# Top.net
KiCad netlist of a schematic drawn in EAGLE
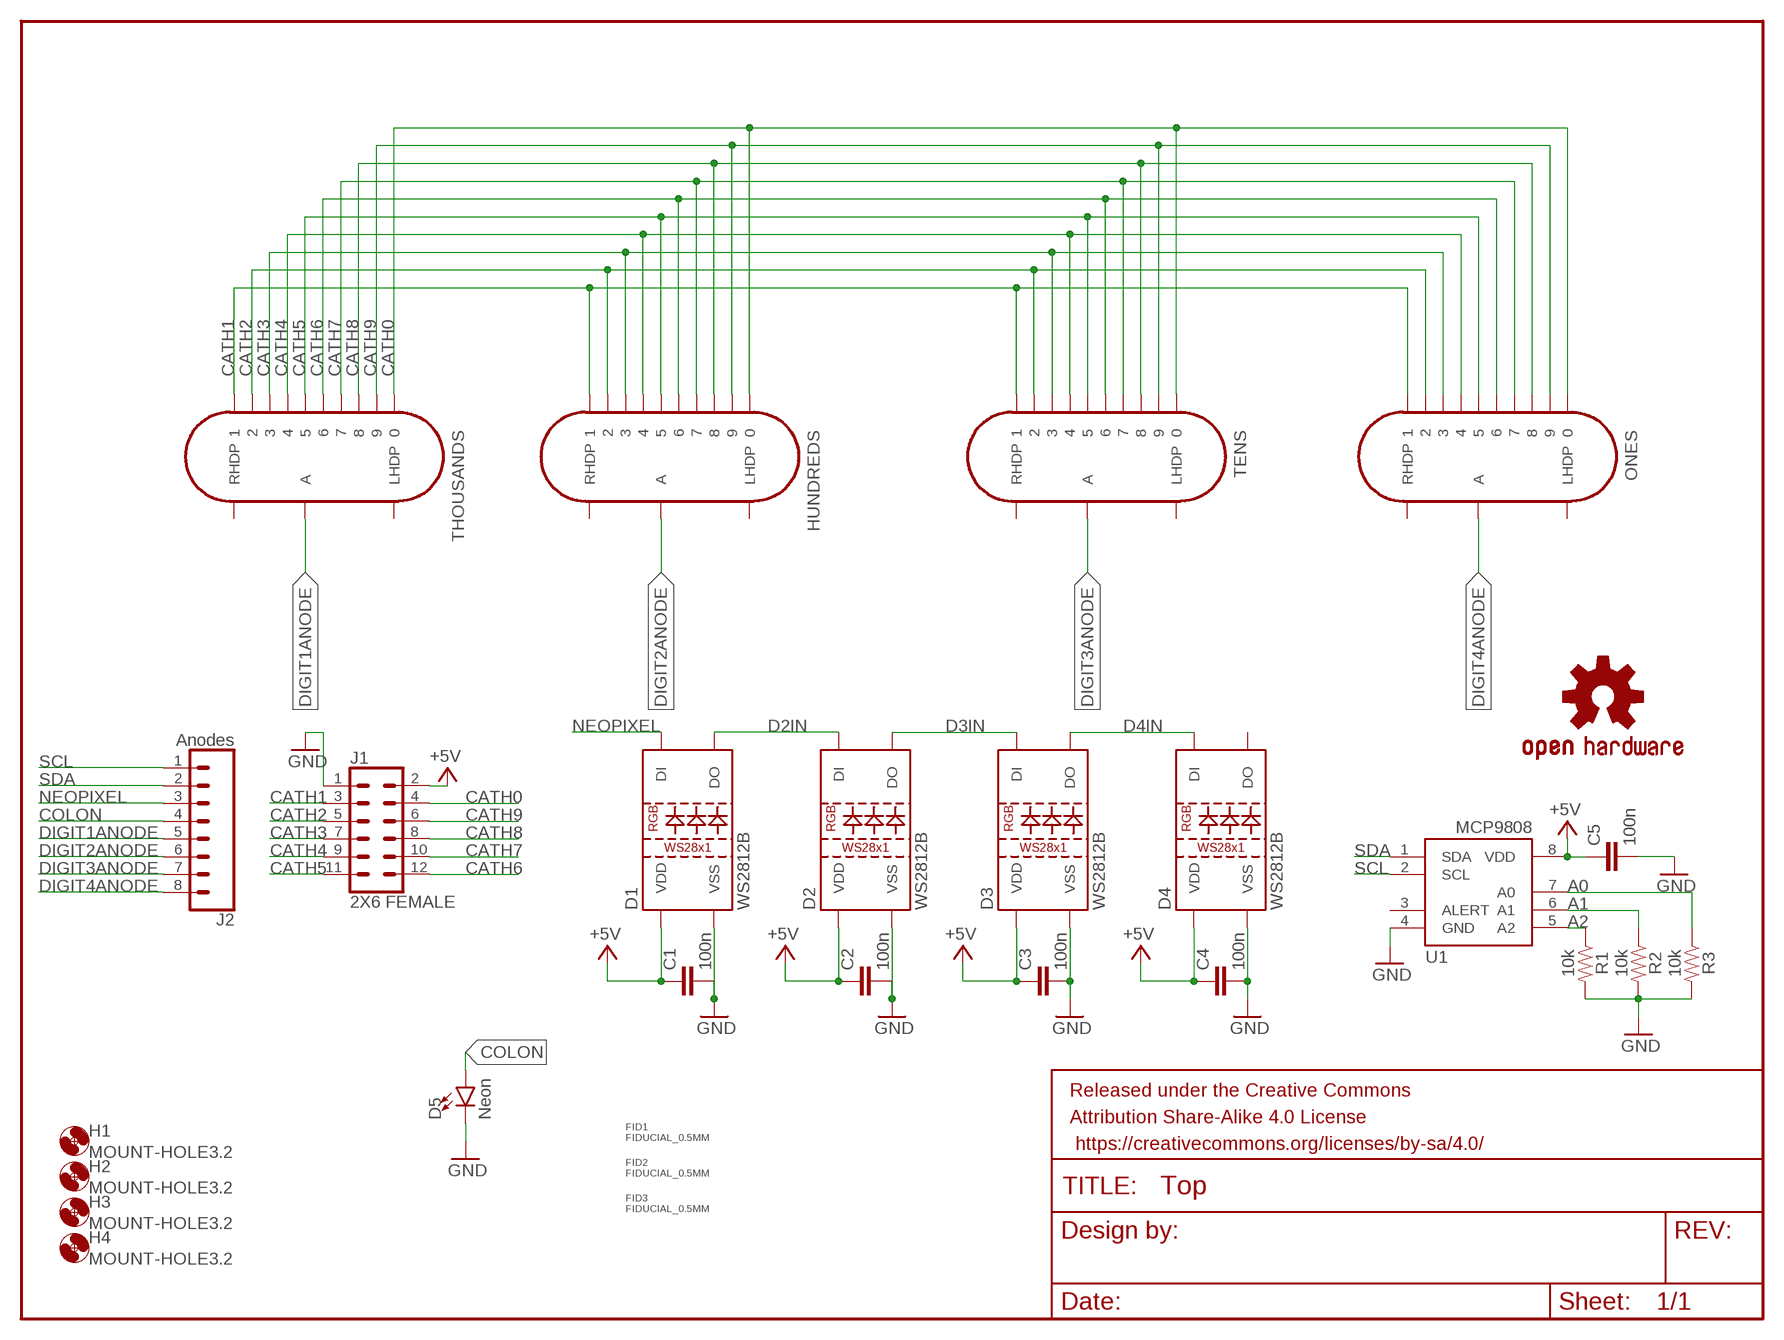
[diagram p0: schematic, sheet 1]

(export (version "E")
  (design (tool "Eeschema 10.0.6"))
  (components
    (comp (ref "C1")
      (value "100n")
      (footprint "eagle-import:0805")
      (libsource (lib "eagle-import") (part "2.2UF-0805-25V-(+80/-20%)"))
    )
    (comp (ref "C2")
      (value "100n")
      (footprint "eagle-import:0805")
      (libsource (lib "eagle-import") (part "2.2UF-0805-25V-(+80/-20%)"))
    )
    (comp (ref "C3")
      (value "100n")
      (footprint "eagle-import:0805")
      (libsource (lib "eagle-import") (part "2.2UF-0805-25V-(+80/-20%)"))
    )
    (comp (ref "C4")
      (value "100n")
      (footprint "eagle-import:0805")
      (libsource (lib "eagle-import") (part "2.2UF-0805-25V-(+80/-20%)"))
    )
    (comp (ref "C5")
      (value "100n")
      (footprint "eagle-import:0805")
      (libsource (lib "eagle-import") (part "2.2UF-0805-25V-(+80/-20%)"))
    )
    (comp (ref "D1")
      (value "WS2812B")
      (footprint "eagle-import:WS2812B")
      (libsource (lib "eagle-import") (part "WS2812B"))
    )
    (comp (ref "D2")
      (value "WS2812B")
      (footprint "eagle-import:WS2812B")
      (libsource (lib "eagle-import") (part "WS2812B"))
    )
    (comp (ref "D3")
      (value "WS2812B")
      (footprint "eagle-import:WS2812B")
      (libsource (lib "eagle-import") (part "WS2812B"))
    )
    (comp (ref "D4")
      (value "WS2812B")
      (footprint "eagle-import:WS2812B")
      (libsource (lib "eagle-import") (part "WS2812B"))
    )
    (comp (ref "D5")
      (value "Neon")
      (footprint "eagle-import:LED_5MM")
      (libsource (lib "eagle-import") (part "LED5MM"))
    )
    (comp (ref "FID1")
      (value "FIDUCIAL_0.5MM")
      (footprint "eagle-import:FIDUCIAL_0.5MM")
      (fields (field (name "HOUSEPART") "NO"))
      (libsource (lib "eagle-import") (part "FIDUCIAL_0.5MM"))
    )
    (comp (ref "FID2")
      (value "FIDUCIAL_0.5MM")
      (footprint "eagle-import:FIDUCIAL_0.5MM")
      (fields (field (name "HOUSEPART") "NO"))
      (libsource (lib "eagle-import") (part "FIDUCIAL_0.5MM"))
    )
    (comp (ref "FID3")
      (value "FIDUCIAL_0.5MM")
      (footprint "eagle-import:FIDUCIAL_0.5MM")
      (fields (field (name "HOUSEPART") "NO"))
      (libsource (lib "eagle-import") (part "FIDUCIAL_0.5MM"))
    )
    (comp (ref "FRAME1")
      (value "FRAME-LETTER")
      (footprint "eagle-import:CREATIVE_COMMONS")
      (libsource (lib "eagle-import") (part "FRAME-LETTER"))
    )
    (comp (ref "H1")
      (value "MOUNT-HOLE3.2")
      (footprint "eagle-import:3,2")
      (libsource (lib "eagle-import") (part "MOUNT-HOLE3.2"))
    )
    (comp (ref "H2")
      (value "MOUNT-HOLE3.2")
      (footprint "eagle-import:3,2")
      (libsource (lib "eagle-import") (part "MOUNT-HOLE3.2"))
    )
    (comp (ref "H3")
      (value "MOUNT-HOLE3.2")
      (footprint "eagle-import:3,2")
      (libsource (lib "eagle-import") (part "MOUNT-HOLE3.2"))
    )
    (comp (ref "H4")
      (value "MOUNT-HOLE3.2")
      (footprint "eagle-import:3,2")
      (libsource (lib "eagle-import") (part "MOUNT-HOLE3.2"))
    )
    (comp (ref "HUNDREDS")
      (value "IN-14")
      (footprint "eagle-import:IN-14")
      (libsource (lib "eagle-import") (part "IN-14"))
    )
    (comp (ref "J1")
      (value "2X6 FEMALE")
      (footprint "eagle-import:2X6_NOSILK")
      (libsource (lib "eagle-import") (part "CONN_06X2NO_SILK"))
    )
    (comp (ref "J2")
      (value "Anodes")
      (footprint "eagle-import:1X08_NO_SILK")
      (libsource (lib "eagle-import") (part "CONN_08NO_SILK_FEMALE_PTH"))
    )
    (comp (ref "LOGO1")
      (value "OSHW-LOGOM")
      (footprint "eagle-import:OSHW-LOGO-M")
      (libsource (lib "eagle-import") (part "OSHW-LOGOM"))
    )
    (comp (ref "ONES")
      (value "IN-14")
      (footprint "eagle-import:IN-14")
      (libsource (lib "eagle-import") (part "IN-14"))
    )
    (comp (ref "R1")
      (value "10k")
      (footprint "eagle-import:0805")
      (libsource (lib "eagle-import") (part "0.75OHM-0805-1/4W-1%"))
    )
    (comp (ref "R2")
      (value "10k")
      (footprint "eagle-import:0805")
      (libsource (lib "eagle-import") (part "0.75OHM-0805-1/4W-1%"))
    )
    (comp (ref "R3")
      (value "10k")
      (footprint "eagle-import:0805")
      (libsource (lib "eagle-import") (part "0.75OHM-0805-1/4W-1%"))
    )
    (comp (ref "TENS")
      (value "IN-14")
      (footprint "eagle-import:IN-14")
      (libsource (lib "eagle-import") (part "IN-14"))
    )
    (comp (ref "THOUSANDS")
      (value "IN-14")
      (footprint "eagle-import:IN-14")
      (libsource (lib "eagle-import") (part "IN-14"))
    )
    (comp (ref "U1")
      (value "MCP9808-E/MS")
      (footprint "eagle-import:MSOP8_0.65MM")
      (libsource (lib "eagle-import") (part "MCP9808-E/MS"))
    )
  )
  (nets
    (net (code "1") (name "+5V") (class "Default")
      (node (ref "C1") (pin "1") (pinfunction "1_1") (pintype "passive"))
      (node (ref "C2") (pin "1") (pinfunction "1_1") (pintype "passive"))
      (node (ref "C3") (pin "1") (pinfunction "1_1") (pintype "passive"))
      (node (ref "C4") (pin "1") (pinfunction "1_1") (pintype "passive"))
      (node (ref "C5") (pin "1") (pinfunction "1_1") (pintype "passive"))
      (node (ref "D1") (pin "1") (pinfunction "VDD_1") (pintype "bidirectional"))
      (node (ref "D2") (pin "1") (pinfunction "VDD_1") (pintype "bidirectional"))
      (node (ref "D3") (pin "1") (pinfunction "VDD_1") (pintype "bidirectional"))
      (node (ref "D4") (pin "1") (pinfunction "VDD_1") (pintype "bidirectional"))
      (node (ref "J1") (pin "2") (pinfunction "2_2") (pintype "passive"))
      (node (ref "U1") (pin "8") (pinfunction "VDD_8") (pintype "power_in"))
    )
    (net (code "2") (name "/A0") (class "Default")
      (node (ref "R3") (pin "1") (pinfunction "1_1") (pintype "passive"))
      (node (ref "U1") (pin "7") (pinfunction "A0_7") (pintype "input"))
    )
    (net (code "3") (name "/A1") (class "Default")
      (node (ref "R2") (pin "1") (pinfunction "1_1") (pintype "passive"))
      (node (ref "U1") (pin "6") (pinfunction "A1_6") (pintype "input"))
    )
    (net (code "4") (name "/A2") (class "Default")
      (node (ref "R1") (pin "1") (pinfunction "1_1") (pintype "passive"))
      (node (ref "U1") (pin "5") (pinfunction "A2_5") (pintype "input"))
    )
    (net (code "5") (name "/CATH0") (class "Default")
      (node (ref "HUNDREDS") (pin "1") (pinfunction "0_1") (pintype "bidirectional"))
      (node (ref "J1") (pin "4") (pinfunction "4_4") (pintype "passive"))
      (node (ref "ONES") (pin "1") (pinfunction "0_1") (pintype "bidirectional"))
      (node (ref "TENS") (pin "1") (pinfunction "0_1") (pintype "bidirectional"))
      (node (ref "THOUSANDS") (pin "1") (pinfunction "0_1") (pintype "bidirectional"))
    )
    (net (code "6") (name "/CATH1") (class "Default")
      (node (ref "HUNDREDS") (pin "0") (pinfunction "1_0") (pintype "bidirectional"))
      (node (ref "J1") (pin "3") (pinfunction "3_3") (pintype "passive"))
      (node (ref "ONES") (pin "0") (pinfunction "1_0") (pintype "bidirectional"))
      (node (ref "TENS") (pin "0") (pinfunction "1_0") (pintype "bidirectional"))
      (node (ref "THOUSANDS") (pin "0") (pinfunction "1_0") (pintype "bidirectional"))
    )
    (net (code "7") (name "/CATH2") (class "Default")
      (node (ref "HUNDREDS") (pin "9") (pinfunction "2_9") (pintype "bidirectional"))
      (node (ref "J1") (pin "5") (pinfunction "5_5") (pintype "passive"))
      (node (ref "ONES") (pin "9") (pinfunction "2_9") (pintype "bidirectional"))
      (node (ref "TENS") (pin "9") (pinfunction "2_9") (pintype "bidirectional"))
      (node (ref "THOUSANDS") (pin "9") (pinfunction "2_9") (pintype "bidirectional"))
    )
    (net (code "8") (name "/CATH3") (class "Default")
      (node (ref "HUNDREDS") (pin "8") (pinfunction "3_8") (pintype "bidirectional"))
      (node (ref "J1") (pin "7") (pinfunction "7_7") (pintype "passive"))
      (node (ref "ONES") (pin "8") (pinfunction "3_8") (pintype "bidirectional"))
      (node (ref "TENS") (pin "8") (pinfunction "3_8") (pintype "bidirectional"))
      (node (ref "THOUSANDS") (pin "8") (pinfunction "3_8") (pintype "bidirectional"))
    )
    (net (code "9") (name "/CATH4") (class "Default")
      (node (ref "HUNDREDS") (pin "7") (pinfunction "4_7") (pintype "bidirectional"))
      (node (ref "J1") (pin "9") (pinfunction "9_9") (pintype "passive"))
      (node (ref "ONES") (pin "7") (pinfunction "4_7") (pintype "bidirectional"))
      (node (ref "TENS") (pin "7") (pinfunction "4_7") (pintype "bidirectional"))
      (node (ref "THOUSANDS") (pin "7") (pinfunction "4_7") (pintype "bidirectional"))
    )
    (net (code "10") (name "/CATH5") (class "Default")
      (node (ref "HUNDREDS") (pin "6") (pinfunction "5_6") (pintype "bidirectional"))
      (node (ref "J1") (pin "11") (pinfunction "11_11") (pintype "passive"))
      (node (ref "ONES") (pin "6") (pinfunction "5_6") (pintype "bidirectional"))
      (node (ref "TENS") (pin "6") (pinfunction "5_6") (pintype "bidirectional"))
      (node (ref "THOUSANDS") (pin "6") (pinfunction "5_6") (pintype "bidirectional"))
    )
    (net (code "11") (name "/CATH6") (class "Default")
      (node (ref "HUNDREDS") (pin "5") (pinfunction "6_5") (pintype "bidirectional"))
      (node (ref "J1") (pin "12") (pinfunction "12_12") (pintype "passive"))
      (node (ref "ONES") (pin "5") (pinfunction "6_5") (pintype "bidirectional"))
      (node (ref "TENS") (pin "5") (pinfunction "6_5") (pintype "bidirectional"))
      (node (ref "THOUSANDS") (pin "5") (pinfunction "6_5") (pintype "bidirectional"))
    )
    (net (code "12") (name "/CATH7") (class "Default")
      (node (ref "HUNDREDS") (pin "4") (pinfunction "7_4") (pintype "bidirectional"))
      (node (ref "J1") (pin "10") (pinfunction "10_10") (pintype "passive"))
      (node (ref "ONES") (pin "4") (pinfunction "7_4") (pintype "bidirectional"))
      (node (ref "TENS") (pin "4") (pinfunction "7_4") (pintype "bidirectional"))
      (node (ref "THOUSANDS") (pin "4") (pinfunction "7_4") (pintype "bidirectional"))
    )
    (net (code "13") (name "/CATH8") (class "Default")
      (node (ref "HUNDREDS") (pin "3") (pinfunction "8_3") (pintype "bidirectional"))
      (node (ref "J1") (pin "8") (pinfunction "8_8") (pintype "passive"))
      (node (ref "ONES") (pin "3") (pinfunction "8_3") (pintype "bidirectional"))
      (node (ref "TENS") (pin "3") (pinfunction "8_3") (pintype "bidirectional"))
      (node (ref "THOUSANDS") (pin "3") (pinfunction "8_3") (pintype "bidirectional"))
    )
    (net (code "14") (name "/CATH9") (class "Default")
      (node (ref "HUNDREDS") (pin "2") (pinfunction "9_2") (pintype "bidirectional"))
      (node (ref "J1") (pin "6") (pinfunction "6_6") (pintype "passive"))
      (node (ref "ONES") (pin "2") (pinfunction "9_2") (pintype "bidirectional"))
      (node (ref "TENS") (pin "2") (pinfunction "9_2") (pintype "bidirectional"))
      (node (ref "THOUSANDS") (pin "2") (pinfunction "9_2") (pintype "bidirectional"))
    )
    (net (code "15") (name "/D2IN") (class "Default")
      (node (ref "D1") (pin "2") (pinfunction "DO_2") (pintype "bidirectional"))
      (node (ref "D2") (pin "4") (pinfunction "DI_4") (pintype "bidirectional"))
    )
    (net (code "16") (name "/D3IN") (class "Default")
      (node (ref "D2") (pin "2") (pinfunction "DO_2") (pintype "bidirectional"))
      (node (ref "D3") (pin "4") (pinfunction "DI_4") (pintype "bidirectional"))
    )
    (net (code "17") (name "/D4IN") (class "Default")
      (node (ref "D3") (pin "2") (pinfunction "DO_2") (pintype "bidirectional"))
      (node (ref "D4") (pin "4") (pinfunction "DI_4") (pintype "bidirectional"))
    )
    (net (code "18") (name "/NEOPIXEL") (class "Default")
      (node (ref "D1") (pin "4") (pinfunction "DI_4") (pintype "bidirectional"))
      (node (ref "J2") (pin "3") (pinfunction "3_3") (pintype "passive"))
    )
    (net (code "19") (name "/SCL") (class "Default")
      (node (ref "J2") (pin "1") (pinfunction "1_1") (pintype "passive"))
      (node (ref "U1") (pin "2") (pinfunction "SCL_2") (pintype "bidirectional"))
    )
    (net (code "20") (name "/SDA") (class "Default")
      (node (ref "J2") (pin "2") (pinfunction "2_2") (pintype "passive"))
      (node (ref "U1") (pin "1") (pinfunction "SDA_1") (pintype "bidirectional"))
    )
    (net (code "21") (name "COLON") (class "Default")
      (node (ref "D5") (pin "A") (pinfunction "A_A") (pintype "passive"))
      (node (ref "J2") (pin "4") (pinfunction "4_4") (pintype "passive"))
    )
    (net (code "22") (name "DIGIT1ANODE") (class "Default")
      (node (ref "J2") (pin "5") (pinfunction "5_5") (pintype "passive"))
      (node (ref "THOUSANDS") (pin "A") (pinfunction "A_A") (pintype "bidirectional"))
    )
    (net (code "23") (name "DIGIT2ANODE") (class "Default")
      (node (ref "HUNDREDS") (pin "A") (pinfunction "A_A") (pintype "bidirectional"))
      (node (ref "J2") (pin "6") (pinfunction "6_6") (pintype "passive"))
    )
    (net (code "24") (name "DIGIT3ANODE") (class "Default")
      (node (ref "J2") (pin "7") (pinfunction "7_7") (pintype "passive"))
      (node (ref "TENS") (pin "A") (pinfunction "A_A") (pintype "bidirectional"))
    )
    (net (code "25") (name "DIGIT4ANODE") (class "Default")
      (node (ref "J2") (pin "8") (pinfunction "8_8") (pintype "passive"))
      (node (ref "ONES") (pin "A") (pinfunction "A_A") (pintype "bidirectional"))
    )
    (net (code "26") (name "GND") (class "Default")
      (node (ref "C1") (pin "2") (pinfunction "2_2") (pintype "passive"))
      (node (ref "C2") (pin "2") (pinfunction "2_2") (pintype "passive"))
      (node (ref "C3") (pin "2") (pinfunction "2_2") (pintype "passive"))
      (node (ref "C4") (pin "2") (pinfunction "2_2") (pintype "passive"))
      (node (ref "C5") (pin "2") (pinfunction "2_2") (pintype "passive"))
      (node (ref "D1") (pin "3") (pinfunction "VSS_3") (pintype "bidirectional"))
      (node (ref "D2") (pin "3") (pinfunction "VSS_3") (pintype "bidirectional"))
      (node (ref "D3") (pin "3") (pinfunction "VSS_3") (pintype "bidirectional"))
      (node (ref "D4") (pin "3") (pinfunction "VSS_3") (pintype "bidirectional"))
      (node (ref "D5") (pin "K") (pinfunction "C_K") (pintype "passive"))
      (node (ref "J1") (pin "1") (pinfunction "1_1") (pintype "passive"))
      (node (ref "R1") (pin "2") (pinfunction "2_2") (pintype "passive"))
      (node (ref "R2") (pin "2") (pinfunction "2_2") (pintype "passive"))
      (node (ref "R3") (pin "2") (pinfunction "2_2") (pintype "passive"))
      (node (ref "U1") (pin "4") (pinfunction "GND_4") (pintype "power_in"))
    )
    (net (code "27") (name "unconnected-(D4-DO-Pad2)") (class "Default")
      (node (ref "D4") (pin "2") (pinfunction "DO_2") (pintype "bidirectional"))
    )
    (net (code "28") (name "unconnected-(HUNDREDS-PadLHDP)") (class "Default")
      (node (ref "HUNDREDS") (pin "LHDP") (pinfunction "LHDP_LHDP") (pintype "bidirectional"))
    )
    (net (code "29") (name "unconnected-(HUNDREDS-PadRHDP)") (class "Default")
      (node (ref "HUNDREDS") (pin "RHDP") (pinfunction "RHDP_RHDP") (pintype "bidirectional"))
    )
    (net (code "30") (name "unconnected-(ONES-PadLHDP)") (class "Default")
      (node (ref "ONES") (pin "LHDP") (pinfunction "LHDP_LHDP") (pintype "bidirectional"))
    )
    (net (code "31") (name "unconnected-(ONES-PadRHDP)") (class "Default")
      (node (ref "ONES") (pin "RHDP") (pinfunction "RHDP_RHDP") (pintype "bidirectional"))
    )
    (net (code "32") (name "unconnected-(TENS-PadLHDP)") (class "Default")
      (node (ref "TENS") (pin "LHDP") (pinfunction "LHDP_LHDP") (pintype "bidirectional"))
    )
    (net (code "33") (name "unconnected-(TENS-PadRHDP)") (class "Default")
      (node (ref "TENS") (pin "RHDP") (pinfunction "RHDP_RHDP") (pintype "bidirectional"))
    )
    (net (code "34") (name "unconnected-(THOUSANDS-PadLHDP)") (class "Default")
      (node (ref "THOUSANDS") (pin "LHDP") (pinfunction "LHDP_LHDP") (pintype "bidirectional"))
    )
    (net (code "35") (name "unconnected-(THOUSANDS-PadRHDP)") (class "Default")
      (node (ref "THOUSANDS") (pin "RHDP") (pinfunction "RHDP_RHDP") (pintype "bidirectional"))
    )
    (net (code "36") (name "unconnected-(U1-ALERT-Pad3)") (class "Default")
      (node (ref "U1") (pin "3") (pinfunction "ALERT_3") (pintype "open_collector"))
    )
  )
)
